# Sheet1.net
KiCad netlist of a schematic drawn in Altium Designer
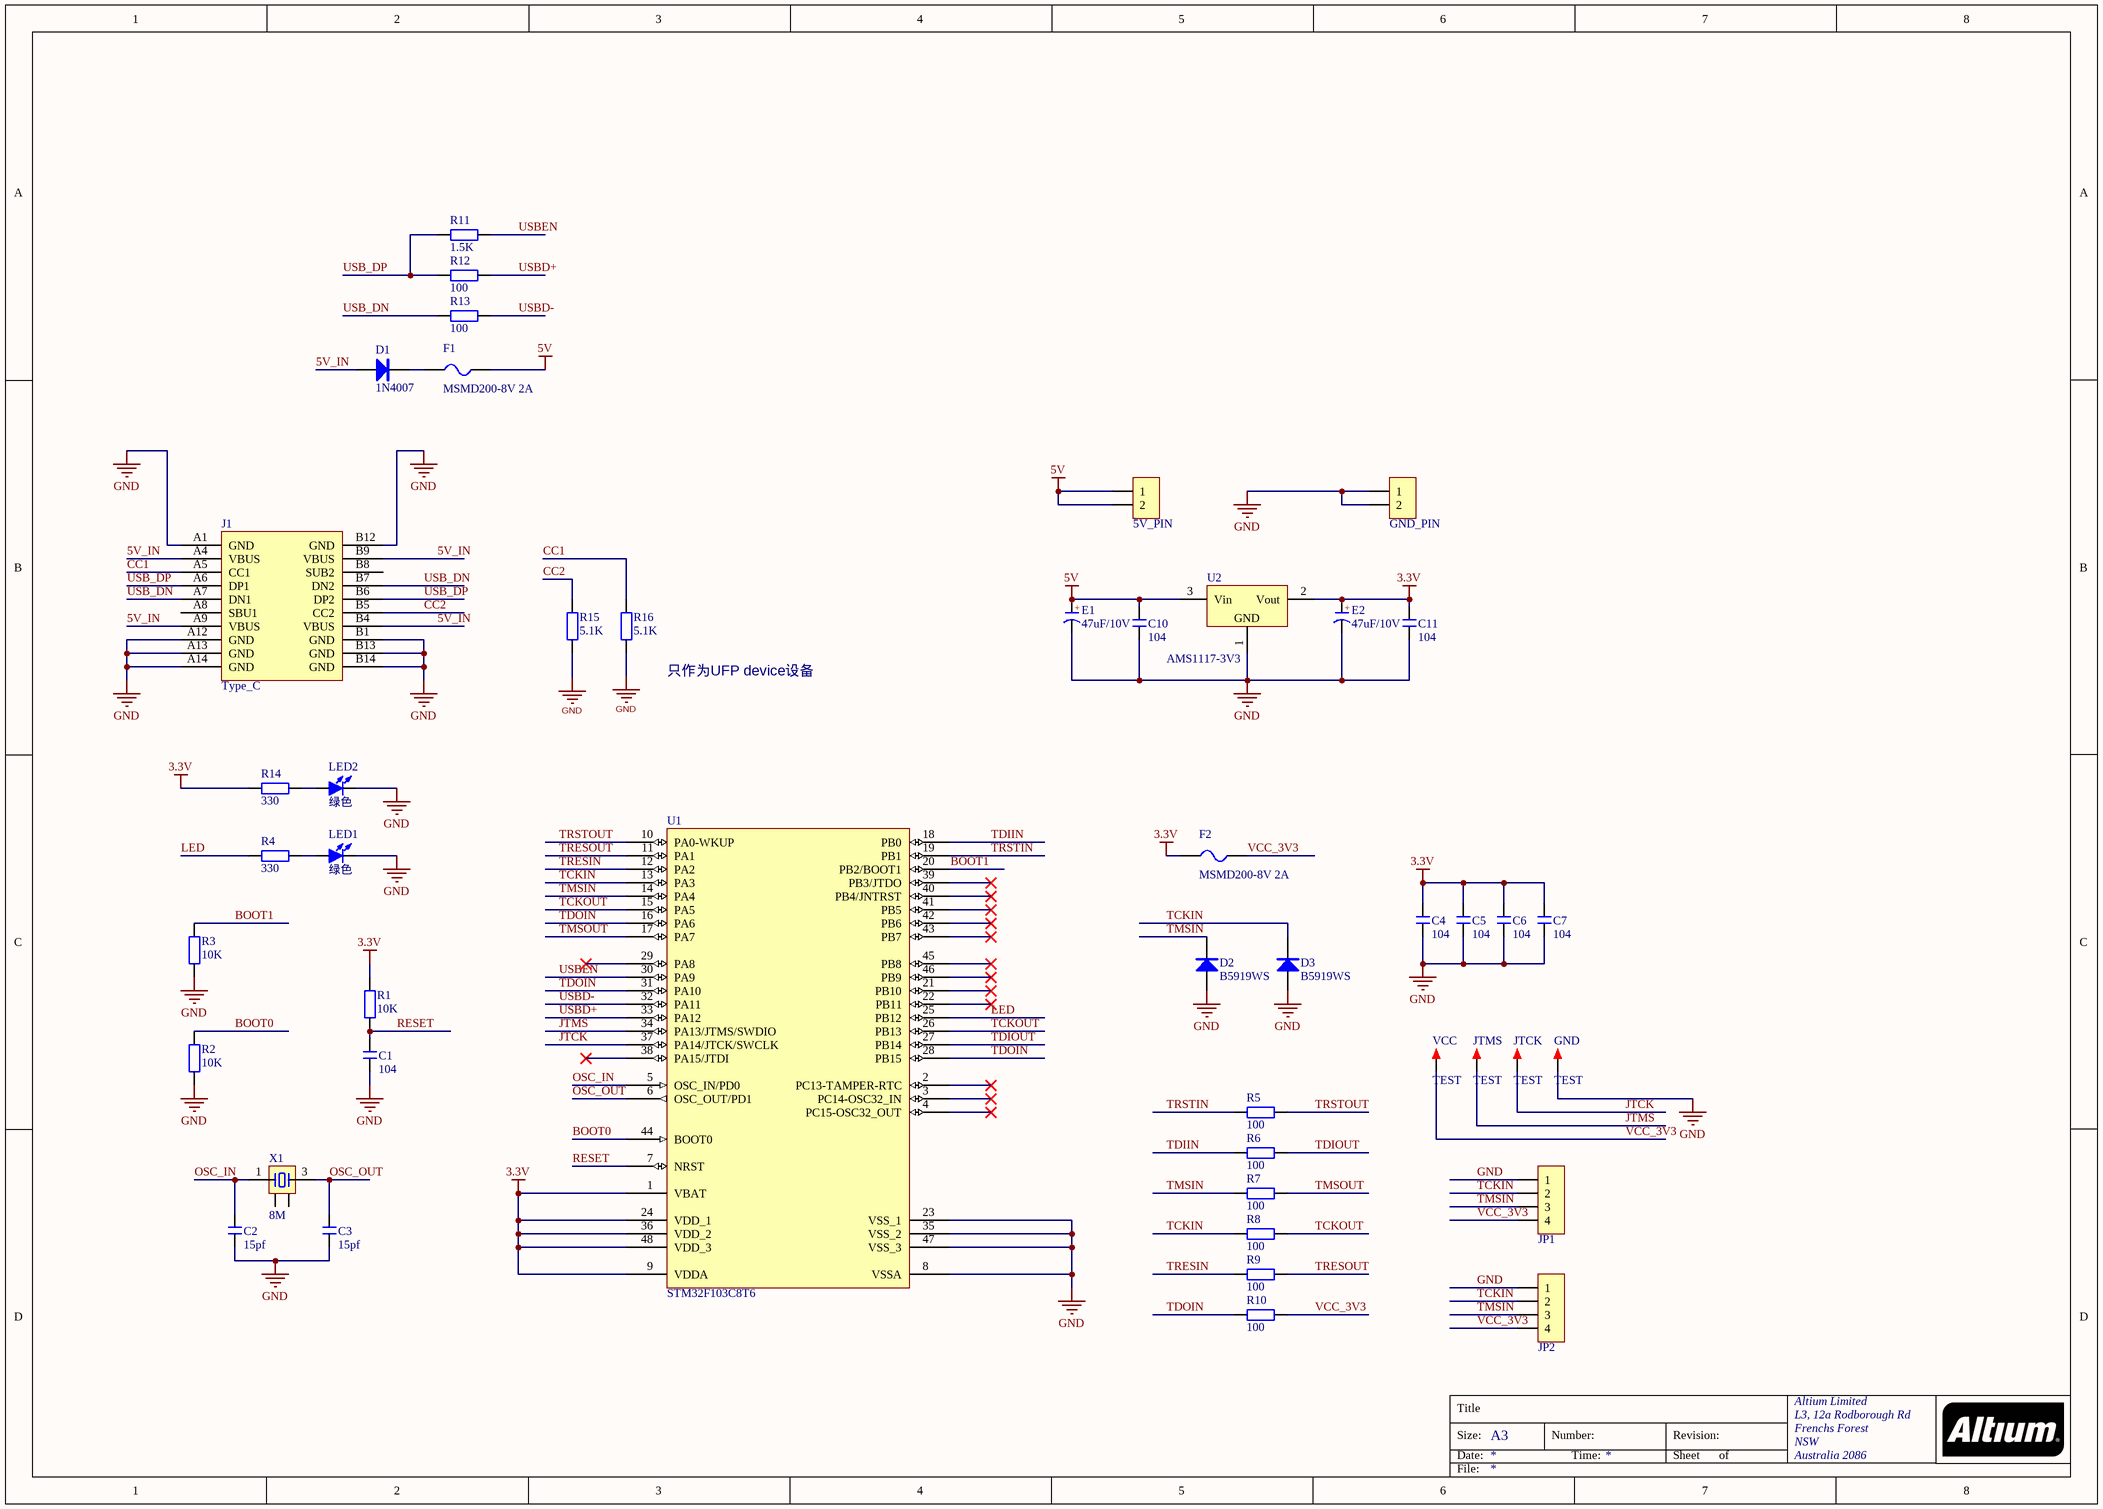
[diagram p0: Sheet1.SchDoc]

(export (version "E")
  (design (tool "Eeschema 10.0.6"))
  (components
    (comp (ref "5V_PIN")
      (value "HDR-1X2")
      (footprint "HDR2.54-LI-2P")
      (description "2P接插件")
      (fields (field (name "版权归属") "源创客"))
      (libsource (lib "4.5   - 接插件-脚距2.54") (part "Header 2"))
    )
    (comp (ref "C1")
      (value "104")
      (footprint "C 0603_L")
      (description "无极性贴片电容")
      (fields (field (name "版权归属") "源创客"))
      (libsource (lib "3.1   - 电阻-电容-电感") (part "C"))
    )
    (comp (ref "C2")
      (value "15pf")
      (footprint "C 0603_L")
      (description "无极性贴片电容")
      (fields (field (name "版权归属") "源创客"))
      (libsource (lib "3.1   - 电阻-电容-电感") (part "C"))
    )
    (comp (ref "C3")
      (value "15pf")
      (footprint "C 0603_L")
      (description "无极性贴片电容")
      (fields (field (name "版权归属") "源创客"))
      (libsource (lib "3.1   - 电阻-电容-电感") (part "C"))
    )
    (comp (ref "C4")
      (value "104")
      (footprint "C 0603_L")
      (description "无极性贴片电容")
      (fields (field (name "版权归属") "源创客"))
      (libsource (lib "3.1   - 电阻-电容-电感") (part "C"))
    )
    (comp (ref "C5")
      (value "104")
      (footprint "C 0603_L")
      (description "无极性贴片电容")
      (fields (field (name "版权归属") "源创客"))
      (libsource (lib "3.1   - 电阻-电容-电感") (part "C"))
    )
    (comp (ref "C6")
      (value "104")
      (footprint "C 0603_L")
      (description "无极性贴片电容")
      (fields (field (name "版权归属") "源创客"))
      (libsource (lib "3.1   - 电阻-电容-电感") (part "C"))
    )
    (comp (ref "C7")
      (value "104")
      (footprint "C 0603_L")
      (description "无极性贴片电容")
      (fields (field (name "版权归属") "源创客"))
      (libsource (lib "3.1   - 电阻-电容-电感") (part "C"))
    )
    (comp (ref "C10")
      (value "104")
      (footprint "C 0603_L")
      (description "无极性贴片电容")
      (fields (field (name "版权归属") "源创客"))
      (libsource (lib "3.1   - 电阻-电容-电感") (part "C"))
    )
    (comp (ref "C11")
      (value "104")
      (footprint "C 0603_L")
      (description "无极性贴片电容")
      (fields (field (name "版权归属") "源创客"))
      (libsource (lib "3.1   - 电阻-电容-电感") (part "C"))
    )
    (comp (ref "D1")
      (value "1N4007")
      (footprint "SOD-123")
      (description "整流二极管")
      (fields (field (name "版权归属") "源创客"))
      (libsource (lib "8.1   - 二极管-整流桥") (part "1N4007"))
    )
    (comp (ref "D2")
      (value "B5919WS")
      (footprint "SOD-323")
      (description "肖特基二极管")
      (fields (field (name "版权归属") "源创客"))
      (libsource (lib "8.1   - 二极管-整流桥") (part "1N5819"))
    )
    (comp (ref "D3")
      (value "B5919WS")
      (footprint "SOD-323")
      (description "肖特基二极管")
      (fields (field (name "版权归属") "源创客"))
      (libsource (lib "8.1   - 二极管-整流桥") (part "1N5819"))
    )
    (comp (ref "E1")
      (value "47uF/10V")
      (footprint "CD B(3528)")
      (description "贴片钽电容")
      (fields (field (name "版权归属") "源创客"))
      (libsource (lib "3.1   - 电阻-电容-电感") (part "C-CD"))
    )
    (comp (ref "E2")
      (value "47uF/10V")
      (footprint "CD B(3528)")
      (description "贴片钽电容")
      (fields (field (name "版权归属") "源创客"))
      (libsource (lib "3.1   - 电阻-电容-电感") (part "C-CD"))
    )
    (comp (ref "F1")
      (value "MSMD200-8V 2A")
      (footprint "FU 0805")
      (description "贴片保险丝")
      (fields (field (name "版权归属") "源创客"))
      (libsource (lib "10.1 - 保险丝-晶振") (part "FU"))
    )
    (comp (ref "F2")
      (value "MSMD200-8V 2A")
      (footprint "FU 0805")
      (description "贴片保险丝")
      (fields (field (name "版权归属") "源创客"))
      (libsource (lib "10.1 - 保险丝-晶振") (part "FU"))
    )
    (comp (ref "GND")
      (value "TEST")
      (footprint "TEST 1.4")
      (description "测试点")
      (fields (field (name "版权归属") "源创客"))
      (libsource (lib "15.1 - 未分类器件") (part "TEST"))
    )
    (comp (ref "GND_PIN")
      (value "HDR-1X2")
      (footprint "HDR2.54-LI-2P")
      (description "2P接插件")
      (fields (field (name "版权归属") "源创客"))
      (libsource (lib "4.5   - 接插件-脚距2.54") (part "Header 2"))
    )
    (comp (ref "J1")
      (value "Type_C")
      (footprint "TYPE-C-16P")
      (description "厂家：乐沪，型号：USB TYPE C 16PF")
      (libsource (lib "Pipe_HEAT_TEST") (part "Type_C"))
    )
    (comp (ref "JP1")
      (value "HDR-1X4")
      (footprint "MX 1.25-WI-4P")
      (description "4P接插件")
      (fields (field (name "版权归属") "源创客"))
      (libsource (lib "4.2   - 接插件-脚距1.25") (part "Header 4"))
    )
    (comp (ref "JP2")
      (value "HDR-1X4")
      (footprint "XH2.54-WI-4P")
      (description "4P接插件")
      (fields (field (name "版权归属") "源创客"))
      (libsource (lib "4.5   - 接插件-脚距2.54") (part "Header 4"))
    )
    (comp (ref "JTCK")
      (value "TEST")
      (footprint "TEST 1.4")
      (description "测试点")
      (fields (field (name "版权归属") "源创客"))
      (libsource (lib "15.1 - 未分类器件") (part "TEST"))
    )
    (comp (ref "JTMS")
      (value "TEST")
      (footprint "TEST 1.4")
      (description "测试点")
      (fields (field (name "版权归属") "源创客"))
      (libsource (lib "15.1 - 未分类器件") (part "TEST"))
    )
    (comp (ref "LED1")
      (value "绿色")
      (footprint "LED 0805G")
      (description "贴片LED")
      (fields (field (name "版权归属") "源创客"))
      (libsource (lib "9.1   - LED") (part "LED-SMD"))
    )
    (comp (ref "LED2")
      (value "绿色")
      (footprint "LED 0805G")
      (description "贴片LED")
      (fields (field (name "版权归属") "源创客"))
      (libsource (lib "9.1   - LED") (part "LED-SMD"))
    )
    (comp (ref "R1")
      (value "10K")
      (footprint "R 0603_L")
      (description "贴片电阻")
      (fields (field (name "版权归属") "源创客"))
      (libsource (lib "3.1   - 电阻-电容-电感") (part "R"))
    )
    (comp (ref "R2")
      (value "10K")
      (footprint "R 0603_L")
      (description "贴片电阻")
      (fields (field (name "版权归属") "源创客"))
      (libsource (lib "3.1   - 电阻-电容-电感") (part "R"))
    )
    (comp (ref "R3")
      (value "10K")
      (footprint "R 0603_L")
      (description "贴片电阻")
      (fields (field (name "版权归属") "源创客"))
      (libsource (lib "3.1   - 电阻-电容-电感") (part "R"))
    )
    (comp (ref "R4")
      (value "330")
      (footprint "R 0603_L")
      (description "贴片电阻")
      (fields (field (name "版权归属") "源创客"))
      (libsource (lib "3.1   - 电阻-电容-电感") (part "R"))
    )
    (comp (ref "R5")
      (value "100")
      (footprint "R 0603_L")
      (description "贴片电阻")
      (fields (field (name "版权归属") "源创客"))
      (libsource (lib "3.1   - 电阻-电容-电感") (part "R"))
    )
    (comp (ref "R6")
      (value "100")
      (footprint "R 0603_L")
      (description "贴片电阻")
      (fields (field (name "版权归属") "源创客"))
      (libsource (lib "3.1   - 电阻-电容-电感") (part "R"))
    )
    (comp (ref "R7")
      (value "100")
      (footprint "R 0603_L")
      (description "贴片电阻")
      (fields (field (name "版权归属") "源创客"))
      (libsource (lib "3.1   - 电阻-电容-电感") (part "R"))
    )
    (comp (ref "R8")
      (value "100")
      (footprint "R 0603_L")
      (description "贴片电阻")
      (fields (field (name "版权归属") "源创客"))
      (libsource (lib "3.1   - 电阻-电容-电感") (part "R"))
    )
    (comp (ref "R9")
      (value "100")
      (footprint "R 0603_L")
      (description "贴片电阻")
      (fields (field (name "版权归属") "源创客"))
      (libsource (lib "3.1   - 电阻-电容-电感") (part "R"))
    )
    (comp (ref "R10")
      (value "100")
      (footprint "R 0603_L")
      (description "贴片电阻")
      (fields (field (name "版权归属") "源创客"))
      (libsource (lib "3.1   - 电阻-电容-电感") (part "R"))
    )
    (comp (ref "R11")
      (value "1.5K")
      (footprint "R 0603_L")
      (description "贴片电阻")
      (fields (field (name "版权归属") "源创客"))
      (libsource (lib "3.1   - 电阻-电容-电感") (part "R"))
    )
    (comp (ref "R12")
      (value "100")
      (footprint "R 0603_L")
      (description "贴片电阻")
      (fields (field (name "版权归属") "源创客"))
      (libsource (lib "3.1   - 电阻-电容-电感") (part "R"))
    )
    (comp (ref "R13")
      (value "100")
      (footprint "R 0603_L")
      (description "贴片电阻")
      (fields (field (name "版权归属") "源创客"))
      (libsource (lib "3.1   - 电阻-电容-电感") (part "R"))
    )
    (comp (ref "R14")
      (value "330")
      (footprint "R 0603_L")
      (description "贴片电阻")
      (fields (field (name "版权归属") "源创客"))
      (libsource (lib "3.1   - 电阻-电容-电感") (part "R"))
    )
    (comp (ref "R15")
      (value "5.1K")
      (footprint "R 0603_L")
      (description "贴片电阻")
      (fields (field (name "版权归属") "源创客"))
      (libsource (lib "3.1   - 电阻-电容-电感") (part "R"))
    )
    (comp (ref "R16")
      (value "5.1K")
      (footprint "R 0603_L")
      (description "贴片电阻")
      (fields (field (name "版权归属") "源创客"))
      (libsource (lib "3.1   - 电阻-电容-电感") (part "R"))
    )
    (comp (ref "U1")
      (value "STM32F103C8T6")
      (footprint "LQFP48_N")
      (description "STM32 ARM-based 32-bit MCU with 64 Kbytes Flash, 48-pin LQFP, Industrial Temperature")
      (fields (field (name "PUBLISHER") "Altium Limited"))
      (libsource (lib "ST Microcontroller 32-Bit STM32") (part "STM32F103C8T6"))
    )
    (comp (ref "U2")
      (value "AMS1117-3V3")
      (footprint "SOT223_L")
      (description "三端稳压芯片")
      (fields (field (name "版权归属") "源创客"))
      (libsource (lib "1.3   - 电源类芯片") (part "AMS1117"))
    )
    (comp (ref "VCC")
      (value "TEST")
      (footprint "TEST 1.4")
      (description "测试点")
      (fields (field (name "版权归属") "源创客"))
      (libsource (lib "15.1 - 未分类器件") (part "TEST"))
    )
    (comp (ref "X1")
      (value "8M")
      (footprint "OSC 5032-4P")
      (description "4脚无源晶振")
      (fields (field (name "版权归属") "源创客"))
      (libsource (lib "10.1 - 保险丝-晶振") (part "XTAL-4P"))
    )
  )
  (nets
    (net (code "1") (name "/5V_IN") (class "Default")
      (node (ref "D1") (pin "1") (pinfunction "A_1") (pintype "passive"))
      (node (ref "J1") (pin "A4") (pinfunction "VBUS_A4") (pintype "passive"))
      (node (ref "J1") (pin "A9") (pinfunction "VBUS_A9") (pintype "passive"))
      (node (ref "J1") (pin "B4") (pinfunction "VBUS_B4") (pintype "passive"))
      (node (ref "J1") (pin "B9") (pinfunction "VBUS_B9") (pintype "passive"))
    )
    (net (code "2") (name "/BOOT0") (class "Default")
      (node (ref "R2") (pin "1") (pinfunction "1_1") (pintype "passive"))
      (node (ref "U1") (pin "44") (pinfunction "BOOT0_44") (pintype "input"))
    )
    (net (code "3") (name "/BOOT1") (class "Default")
      (node (ref "R3") (pin "1") (pinfunction "1_1") (pintype "passive"))
      (node (ref "U1") (pin "20") (pinfunction "PB2/BOOT1_20") (pintype "bidirectional"))
    )
    (net (code "4") (name "/CC1") (class "Default")
      (node (ref "J1") (pin "A5") (pinfunction "CC1_A5") (pintype "passive"))
      (node (ref "R16") (pin "1") (pinfunction "1_1") (pintype "passive"))
    )
    (net (code "5") (name "/CC2") (class "Default")
      (node (ref "J1") (pin "B5") (pinfunction "CC2_B5") (pintype "passive"))
      (node (ref "R15") (pin "1") (pinfunction "1_1") (pintype "passive"))
    )
    (net (code "6") (name "/JTCK") (class "Default")
      (node (ref "JTCK") (pin "1") (pinfunction "1_1") (pintype "passive"))
      (node (ref "U1") (pin "37") (pinfunction "PA14/JTCK/SWCLK_37") (pintype "bidirectional"))
    )
    (net (code "7") (name "/JTMS") (class "Default")
      (node (ref "JTMS") (pin "1") (pinfunction "1_1") (pintype "passive"))
      (node (ref "U1") (pin "34") (pinfunction "PA13/JTMS/SWDIO_34") (pintype "bidirectional"))
    )
    (net (code "8") (name "/LED") (class "Default")
      (node (ref "R4") (pin "2") (pinfunction "2_2") (pintype "passive"))
      (node (ref "U1") (pin "25") (pinfunction "PB12_25") (pintype "bidirectional"))
    )
    (net (code "9") (name "/OSC_IN") (class "Default")
      (node (ref "C2") (pin "2") (pinfunction "2_2") (pintype "passive"))
      (node (ref "U1") (pin "5") (pinfunction "OSC_IN/PD0_5") (pintype "input"))
      (node (ref "X1") (pin "1") (pinfunction "1_1") (pintype "passive"))
    )
    (net (code "10") (name "/OSC_OUT") (class "Default")
      (node (ref "C3") (pin "2") (pinfunction "2_2") (pintype "passive"))
      (node (ref "U1") (pin "6") (pinfunction "OSC_OUT/PD1_6") (pintype "output"))
      (node (ref "X1") (pin "3") (pinfunction "3_3") (pintype "passive"))
    )
    (net (code "11") (name "/RESET") (class "Default")
      (node (ref "C1") (pin "2") (pinfunction "2_2") (pintype "passive"))
      (node (ref "R1") (pin "1") (pinfunction "1_1") (pintype "passive"))
      (node (ref "U1") (pin "7") (pinfunction "NRST_7") (pintype "bidirectional"))
    )
    (net (code "12") (name "/TCKIN") (class "Default")
      (node (ref "D3") (pin "2") (pinfunction "K_2") (pintype "passive"))
      (node (ref "JP1") (pin "2") (pinfunction "2_2") (pintype "passive"))
      (node (ref "JP2") (pin "2") (pinfunction "2_2") (pintype "passive"))
      (node (ref "R8") (pin "2") (pinfunction "2_2") (pintype "passive"))
      (node (ref "U1") (pin "13") (pinfunction "PA3_13") (pintype "bidirectional"))
    )
    (net (code "13") (name "/TCKOUT") (class "Default")
      (node (ref "R8") (pin "1") (pinfunction "1_1") (pintype "passive"))
      (node (ref "U1") (pin "15") (pinfunction "PA5_15") (pintype "bidirectional"))
      (node (ref "U1") (pin "26") (pinfunction "PB13_26") (pintype "bidirectional"))
    )
    (net (code "14") (name "/TDIIN") (class "Default")
      (node (ref "R6") (pin "2") (pinfunction "2_2") (pintype "passive"))
      (node (ref "U1") (pin "18") (pinfunction "PB0_18") (pintype "bidirectional"))
    )
    (net (code "15") (name "/TDIOUT") (class "Default")
      (node (ref "R6") (pin "1") (pinfunction "1_1") (pintype "passive"))
      (node (ref "U1") (pin "27") (pinfunction "PB14_27") (pintype "bidirectional"))
    )
    (net (code "16") (name "/TDOIN") (class "Default")
      (node (ref "R10") (pin "2") (pinfunction "2_2") (pintype "passive"))
      (node (ref "U1") (pin "16") (pinfunction "PA6_16") (pintype "bidirectional"))
      (node (ref "U1") (pin "28") (pinfunction "PB15_28") (pintype "bidirectional"))
      (node (ref "U1") (pin "31") (pinfunction "PA10_31") (pintype "bidirectional"))
    )
    (net (code "17") (name "/TMSIN") (class "Default")
      (node (ref "D2") (pin "2") (pinfunction "K_2") (pintype "passive"))
      (node (ref "JP1") (pin "3") (pinfunction "3_3") (pintype "passive"))
      (node (ref "JP2") (pin "3") (pinfunction "3_3") (pintype "passive"))
      (node (ref "R7") (pin "2") (pinfunction "2_2") (pintype "passive"))
      (node (ref "U1") (pin "14") (pinfunction "PA4_14") (pintype "bidirectional"))
    )
    (net (code "18") (name "/TMSOUT") (class "Default")
      (node (ref "R7") (pin "1") (pinfunction "1_1") (pintype "passive"))
      (node (ref "U1") (pin "17") (pinfunction "PA7_17") (pintype "bidirectional"))
    )
    (net (code "19") (name "/TRESIN") (class "Default")
      (node (ref "R9") (pin "2") (pinfunction "2_2") (pintype "passive"))
      (node (ref "U1") (pin "12") (pinfunction "PA2_12") (pintype "bidirectional"))
    )
    (net (code "20") (name "/TRESOUT") (class "Default")
      (node (ref "R9") (pin "1") (pinfunction "1_1") (pintype "passive"))
      (node (ref "U1") (pin "11") (pinfunction "PA1_11") (pintype "bidirectional"))
    )
    (net (code "21") (name "/TRSTIN") (class "Default")
      (node (ref "R5") (pin "2") (pinfunction "2_2") (pintype "passive"))
      (node (ref "U1") (pin "19") (pinfunction "PB1_19") (pintype "bidirectional"))
    )
    (net (code "22") (name "/TRSTOUT") (class "Default")
      (node (ref "R5") (pin "1") (pinfunction "1_1") (pintype "passive"))
      (node (ref "U1") (pin "10") (pinfunction "PA0-WKUP_10") (pintype "bidirectional"))
    )
    (net (code "23") (name "/USBD+") (class "Default")
      (node (ref "R12") (pin "1") (pinfunction "1_1") (pintype "passive"))
      (node (ref "U1") (pin "33") (pinfunction "PA12_33") (pintype "bidirectional"))
    )
    (net (code "24") (name "/USBD-") (class "Default")
      (node (ref "R13") (pin "1") (pinfunction "1_1") (pintype "passive"))
      (node (ref "U1") (pin "32") (pinfunction "PA11_32") (pintype "bidirectional"))
    )
    (net (code "25") (name "/USBEN") (class "Default")
      (node (ref "R11") (pin "1") (pinfunction "1_1") (pintype "passive"))
      (node (ref "U1") (pin "30") (pinfunction "PA9_30") (pintype "bidirectional"))
    )
    (net (code "26") (name "/USB_DN") (class "Default")
      (node (ref "J1") (pin "A7") (pinfunction "DN1_A7") (pintype "passive"))
      (node (ref "J1") (pin "B7") (pinfunction "DN2_B7") (pintype "passive"))
      (node (ref "R13") (pin "2") (pinfunction "2_2") (pintype "passive"))
    )
    (net (code "27") (name "/USB_DP") (class "Default")
      (node (ref "J1") (pin "A6") (pinfunction "DP1_A6") (pintype "passive"))
      (node (ref "J1") (pin "B6") (pinfunction "DP2_B6") (pintype "passive"))
      (node (ref "R11") (pin "2") (pinfunction "2_2") (pintype "passive"))
      (node (ref "R12") (pin "2") (pinfunction "2_2") (pintype "passive"))
    )
    (net (code "28") (name "/VCC_3V3") (class "Default")
      (node (ref "F2") (pin "2") (pinfunction "2_2") (pintype "passive"))
      (node (ref "JP1") (pin "4") (pinfunction "4_4") (pintype "passive"))
      (node (ref "JP2") (pin "4") (pinfunction "4_4") (pintype "passive"))
      (node (ref "R10") (pin "1") (pinfunction "1_1") (pintype "passive"))
      (node (ref "VCC") (pin "1") (pinfunction "1_1") (pintype "passive"))
    )
    (net (code "29") (name "3.3V") (class "Default")
      (node (ref "C11") (pin "2") (pinfunction "2_2") (pintype "passive"))
      (node (ref "C4") (pin "2") (pinfunction "2_2") (pintype "passive"))
      (node (ref "C5") (pin "2") (pinfunction "2_2") (pintype "passive"))
      (node (ref "C6") (pin "2") (pinfunction "2_2") (pintype "passive"))
      (node (ref "C7") (pin "2") (pinfunction "2_2") (pintype "passive"))
      (node (ref "E2") (pin "1") (pinfunction "A_1") (pintype "passive"))
      (node (ref "F2") (pin "1") (pinfunction "1_1") (pintype "passive"))
      (node (ref "R1") (pin "2") (pinfunction "2_2") (pintype "passive"))
      (node (ref "R14") (pin "2") (pinfunction "2_2") (pintype "passive"))
      (node (ref "U1") (pin "1") (pinfunction "VBAT_1") (pintype "power_in"))
      (node (ref "U1") (pin "24") (pinfunction "VDD_1_24") (pintype "power_in"))
      (node (ref "U1") (pin "36") (pinfunction "VDD_2_36") (pintype "power_in"))
      (node (ref "U1") (pin "48") (pinfunction "VDD_3_48") (pintype "power_in"))
      (node (ref "U1") (pin "9") (pinfunction "VDDA_9") (pintype "power_in"))
      (node (ref "U2") (pin "2") (pinfunction "Vout_2") (pintype "passive"))
    )
    (net (code "30") (name "5V") (class "Default")
      (node (ref "5V_PIN") (pin "1") (pinfunction "1_1") (pintype "passive"))
      (node (ref "5V_PIN") (pin "2") (pinfunction "2_2") (pintype "passive"))
      (node (ref "C10") (pin "2") (pinfunction "2_2") (pintype "passive"))
      (node (ref "E1") (pin "1") (pinfunction "A_1") (pintype "passive"))
      (node (ref "F1") (pin "2") (pinfunction "2_2") (pintype "passive"))
      (node (ref "U2") (pin "3") (pinfunction "Vin_3") (pintype "passive"))
    )
    (net (code "31") (name "GND") (class "Default")
      (node (ref "C1") (pin "1") (pinfunction "1_1") (pintype "passive"))
      (node (ref "C10") (pin "1") (pinfunction "1_1") (pintype "passive"))
      (node (ref "C11") (pin "1") (pinfunction "1_1") (pintype "passive"))
      (node (ref "C2") (pin "1") (pinfunction "1_1") (pintype "passive"))
      (node (ref "C3") (pin "1") (pinfunction "1_1") (pintype "passive"))
      (node (ref "C4") (pin "1") (pinfunction "1_1") (pintype "passive"))
      (node (ref "C5") (pin "1") (pinfunction "1_1") (pintype "passive"))
      (node (ref "C6") (pin "1") (pinfunction "1_1") (pintype "passive"))
      (node (ref "C7") (pin "1") (pinfunction "1_1") (pintype "passive"))
      (node (ref "D2") (pin "1") (pinfunction "A_1") (pintype "passive"))
      (node (ref "D3") (pin "1") (pinfunction "A_1") (pintype "passive"))
      (node (ref "E1") (pin "2") (pinfunction "K_2") (pintype "passive"))
      (node (ref "E2") (pin "2") (pinfunction "K_2") (pintype "passive"))
      (node (ref "GND") (pin "1") (pinfunction "1_1") (pintype "passive"))
      (node (ref "GND_PIN") (pin "1") (pinfunction "1_1") (pintype "passive"))
      (node (ref "GND_PIN") (pin "2") (pinfunction "2_2") (pintype "passive"))
      (node (ref "J1") (pin "A1") (pinfunction "GND_A1") (pintype "passive"))
      (node (ref "J1") (pin "A12") (pinfunction "GND_A12") (pintype "passive"))
      (node (ref "J1") (pin "A13") (pinfunction "GND_A13") (pintype "passive"))
      (node (ref "J1") (pin "A14") (pinfunction "GND_A14") (pintype "passive"))
      (node (ref "J1") (pin "B1") (pinfunction "GND_B1") (pintype "passive"))
      (node (ref "J1") (pin "B12") (pinfunction "GND_B12") (pintype "passive"))
      (node (ref "J1") (pin "B13") (pinfunction "GND_B13") (pintype "passive"))
      (node (ref "J1") (pin "B14") (pinfunction "GND_B14") (pintype "passive"))
      (node (ref "JP1") (pin "1") (pinfunction "1_1") (pintype "passive"))
      (node (ref "JP2") (pin "1") (pinfunction "1_1") (pintype "passive"))
      (node (ref "LED1") (pin "2") (pinfunction "K_2") (pintype "passive"))
      (node (ref "LED2") (pin "2") (pinfunction "K_2") (pintype "passive"))
      (node (ref "R15") (pin "2") (pinfunction "2_2") (pintype "passive"))
      (node (ref "R16") (pin "2") (pinfunction "2_2") (pintype "passive"))
      (node (ref "R2") (pin "2") (pinfunction "2_2") (pintype "passive"))
      (node (ref "R3") (pin "2") (pinfunction "2_2") (pintype "passive"))
      (node (ref "U1") (pin "23") (pinfunction "VSS_1_23") (pintype "power_in"))
      (node (ref "U1") (pin "35") (pinfunction "VSS_2_35") (pintype "power_in"))
      (node (ref "U1") (pin "47") (pinfunction "VSS_3_47") (pintype "power_in"))
      (node (ref "U1") (pin "8") (pinfunction "VSSA_8") (pintype "power_in"))
      (node (ref "U2") (pin "1") (pinfunction "GND_1") (pintype "passive"))
    )
    (net (code "32") (name "Net-(D1-K)") (class "Default")
      (node (ref "D1") (pin "2") (pinfunction "K_2") (pintype "passive"))
      (node (ref "F1") (pin "1") (pinfunction "1_1") (pintype "passive"))
    )
    (net (code "33") (name "Net-(LED1-A)") (class "Default")
      (node (ref "LED1") (pin "1") (pinfunction "A_1") (pintype "passive"))
      (node (ref "R4") (pin "1") (pinfunction "1_1") (pintype "passive"))
    )
    (net (code "34") (name "Net-(LED2-A)") (class "Default")
      (node (ref "LED2") (pin "1") (pinfunction "A_1") (pintype "passive"))
      (node (ref "R14") (pin "1") (pinfunction "1_1") (pintype "passive"))
    )
    (net (code "35") (name "unconnected-(J1-SBU1-PadA8)") (class "Default")
      (node (ref "J1") (pin "A8") (pinfunction "SBU1_A8") (pintype "passive"))
    )
    (net (code "36") (name "unconnected-(J1-SUB2-PadB8)") (class "Default")
      (node (ref "J1") (pin "B8") (pinfunction "SUB2_B8") (pintype "passive"))
    )
    (net (code "37") (name "unconnected-(U1-PA8-Pad29)") (class "Default")
      (node (ref "U1") (pin "29") (pinfunction "PA8_29") (pintype "bidirectional+no_connect"))
    )
    (net (code "38") (name "unconnected-(U1-PA15{slash}JTDI-Pad38)") (class "Default")
      (node (ref "U1") (pin "38") (pinfunction "PA15/JTDI_38") (pintype "bidirectional+no_connect"))
    )
    (net (code "39") (name "unconnected-(U1-PB3{slash}JTDO-Pad39)") (class "Default")
      (node (ref "U1") (pin "39") (pinfunction "PB3/JTDO_39") (pintype "bidirectional+no_connect"))
    )
    (net (code "40") (name "unconnected-(U1-PB4{slash}JNTRST-Pad40)") (class "Default")
      (node (ref "U1") (pin "40") (pinfunction "PB4/JNTRST_40") (pintype "bidirectional+no_connect"))
    )
    (net (code "41") (name "unconnected-(U1-PB5-Pad41)") (class "Default")
      (node (ref "U1") (pin "41") (pinfunction "PB5_41") (pintype "bidirectional+no_connect"))
    )
    (net (code "42") (name "unconnected-(U1-PB6-Pad42)") (class "Default")
      (node (ref "U1") (pin "42") (pinfunction "PB6_42") (pintype "bidirectional+no_connect"))
    )
    (net (code "43") (name "unconnected-(U1-PB7-Pad43)") (class "Default")
      (node (ref "U1") (pin "43") (pinfunction "PB7_43") (pintype "bidirectional+no_connect"))
    )
    (net (code "44") (name "unconnected-(U1-PB8-Pad45)") (class "Default")
      (node (ref "U1") (pin "45") (pinfunction "PB8_45") (pintype "bidirectional+no_connect"))
    )
    (net (code "45") (name "unconnected-(U1-PB9-Pad46)") (class "Default")
      (node (ref "U1") (pin "46") (pinfunction "PB9_46") (pintype "bidirectional+no_connect"))
    )
    (net (code "46") (name "unconnected-(U1-PB10-Pad21)") (class "Default")
      (node (ref "U1") (pin "21") (pinfunction "PB10_21") (pintype "bidirectional+no_connect"))
    )
    (net (code "47") (name "unconnected-(U1-PB11-Pad22)") (class "Default")
      (node (ref "U1") (pin "22") (pinfunction "PB11_22") (pintype "bidirectional+no_connect"))
    )
    (net (code "48") (name "unconnected-(U1-PC13-TAMPER-RTC-Pad2)") (class "Default")
      (node (ref "U1") (pin "2") (pinfunction "PC13-TAMPER-RTC_2") (pintype "bidirectional+no_connect"))
    )
    (net (code "49") (name "unconnected-(U1-PC14-OSC32_IN-Pad3)") (class "Default")
      (node (ref "U1") (pin "3") (pinfunction "PC14-OSC32_IN_3") (pintype "bidirectional+no_connect"))
    )
    (net (code "50") (name "unconnected-(U1-PC15-OSC32_OUT-Pad4)") (class "Default")
      (node (ref "U1") (pin "4") (pinfunction "PC15-OSC32_OUT_4") (pintype "bidirectional+no_connect"))
    )
    (net (code "51") (name "unconnected-(X1-Pad2)") (class "Default")
      (node (ref "X1") (pin "2") (pinfunction "2_2") (pintype "passive"))
    )
    (net (code "52") (name "unconnected-(X1-Pad4)") (class "Default")
      (node (ref "X1") (pin "4") (pinfunction "4_4") (pintype "passive"))
    )
  )
)
